# ILASButtonSchem.net
KiCad netlist of a schematic drawn in Altium Designer
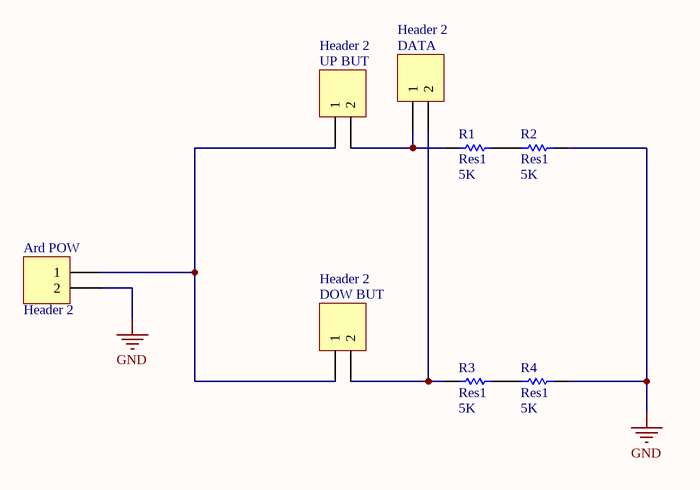
[diagram p0: ILASButtonSchem.SchDoc]

(export (version "E")
  (design (tool "Eeschema 10.0.6"))
  (components
    (comp (ref "Ard POW")
      (value "Header 2")
      (footprint "HDR1X2")
      (description "Header, 2-Pin")
      (fields (field (name "PUBLISHER") "Altium Limited"))
      (libsource (lib "") (part "Header 2_1"))
    )
    (comp (ref "DATA")
      (value "Header 2")
      (footprint "HDR1X2")
      (description "Header, 2-Pin")
      (fields (field (name "PUBLISHER") "Altium Limited"))
      (libsource (lib "Miscellaneous Connectors") (part "Header 2"))
    )
    (comp (ref "DOW BUT")
      (value "Header 2")
      (footprint "HDR1X2")
      (description "Header, 2-Pin")
      (fields (field (name "PUBLISHER") "Altium Limited"))
      (libsource (lib "Miscellaneous Connectors") (part "Header 2"))
    )
    (comp (ref "R1")
      (value "Res1")
      (footprint "AXIAL-0.3")
      (description "Resistor")
      (fields (field (name "ALTIUM_VALUE") "5K") (field (name "PUBLISHER") "Altium Limited"))
      (libsource (lib "Miscellaneous Devices") (part "Res1"))
    )
    (comp (ref "R2")
      (value "Res1")
      (footprint "AXIAL-0.3")
      (description "Resistor")
      (fields (field (name "ALTIUM_VALUE") "5K") (field (name "PUBLISHER") "Altium Limited"))
      (libsource (lib "Miscellaneous Devices") (part "Res1"))
    )
    (comp (ref "R3")
      (value "Res1")
      (footprint "AXIAL-0.3")
      (description "Resistor")
      (fields (field (name "ALTIUM_VALUE") "5K") (field (name "PUBLISHER") "Altium Limited"))
      (libsource (lib "Miscellaneous Devices") (part "Res1"))
    )
    (comp (ref "R4")
      (value "Res1")
      (footprint "AXIAL-0.3")
      (description "Resistor")
      (fields (field (name "ALTIUM_VALUE") "5K") (field (name "PUBLISHER") "Altium Limited"))
      (libsource (lib "Miscellaneous Devices") (part "Res1"))
    )
    (comp (ref "UP BUT")
      (value "Header 2")
      (footprint "HDR1X2")
      (description "Header, 2-Pin")
      (fields (field (name "PUBLISHER") "Altium Limited"))
      (libsource (lib "Miscellaneous Connectors") (part "Header 2"))
    )
  )
  (nets
    (net (code "1") (name "GND") (class "Default")
      (node (ref "Ard POW") (pin "2") (pinfunction "2_2") (pintype "passive"))
      (node (ref "R2") (pin "2") (pinfunction "2_2") (pintype "passive"))
      (node (ref "R4") (pin "2") (pinfunction "2_2") (pintype "passive"))
    )
    (net (code "2") (name "Net-(Ard POW-Pad1)") (class "Default")
      (node (ref "Ard POW") (pin "1") (pinfunction "1_1") (pintype "passive"))
      (node (ref "DOW BUT") (pin "1") (pinfunction "1_1") (pintype "passive"))
      (node (ref "UP BUT") (pin "1") (pinfunction "1_1") (pintype "passive"))
    )
    (net (code "3") (name "Net-(DATA-Pad1)") (class "Default")
      (node (ref "DATA") (pin "1") (pinfunction "1_1") (pintype "passive"))
      (node (ref "R1") (pin "1") (pinfunction "1_1") (pintype "passive"))
      (node (ref "UP BUT") (pin "2") (pinfunction "2_2") (pintype "passive"))
    )
    (net (code "4") (name "Net-(DATA-Pad2)") (class "Default")
      (node (ref "DATA") (pin "2") (pinfunction "2_2") (pintype "passive"))
      (node (ref "DOW BUT") (pin "2") (pinfunction "2_2") (pintype "passive"))
      (node (ref "R3") (pin "1") (pinfunction "1_1") (pintype "passive"))
    )
    (net (code "5") (name "Net-(R1-Pad2)") (class "Default")
      (node (ref "R1") (pin "2") (pinfunction "2_2") (pintype "passive"))
      (node (ref "R2") (pin "1") (pinfunction "1_1") (pintype "passive"))
    )
    (net (code "6") (name "Net-(R3-Pad2)") (class "Default")
      (node (ref "R3") (pin "2") (pinfunction "2_2") (pintype "passive"))
      (node (ref "R4") (pin "1") (pinfunction "1_1") (pintype "passive"))
    )
  )
)
